# Connector.net
KiCad netlist of a schematic drawn in Altium Designer
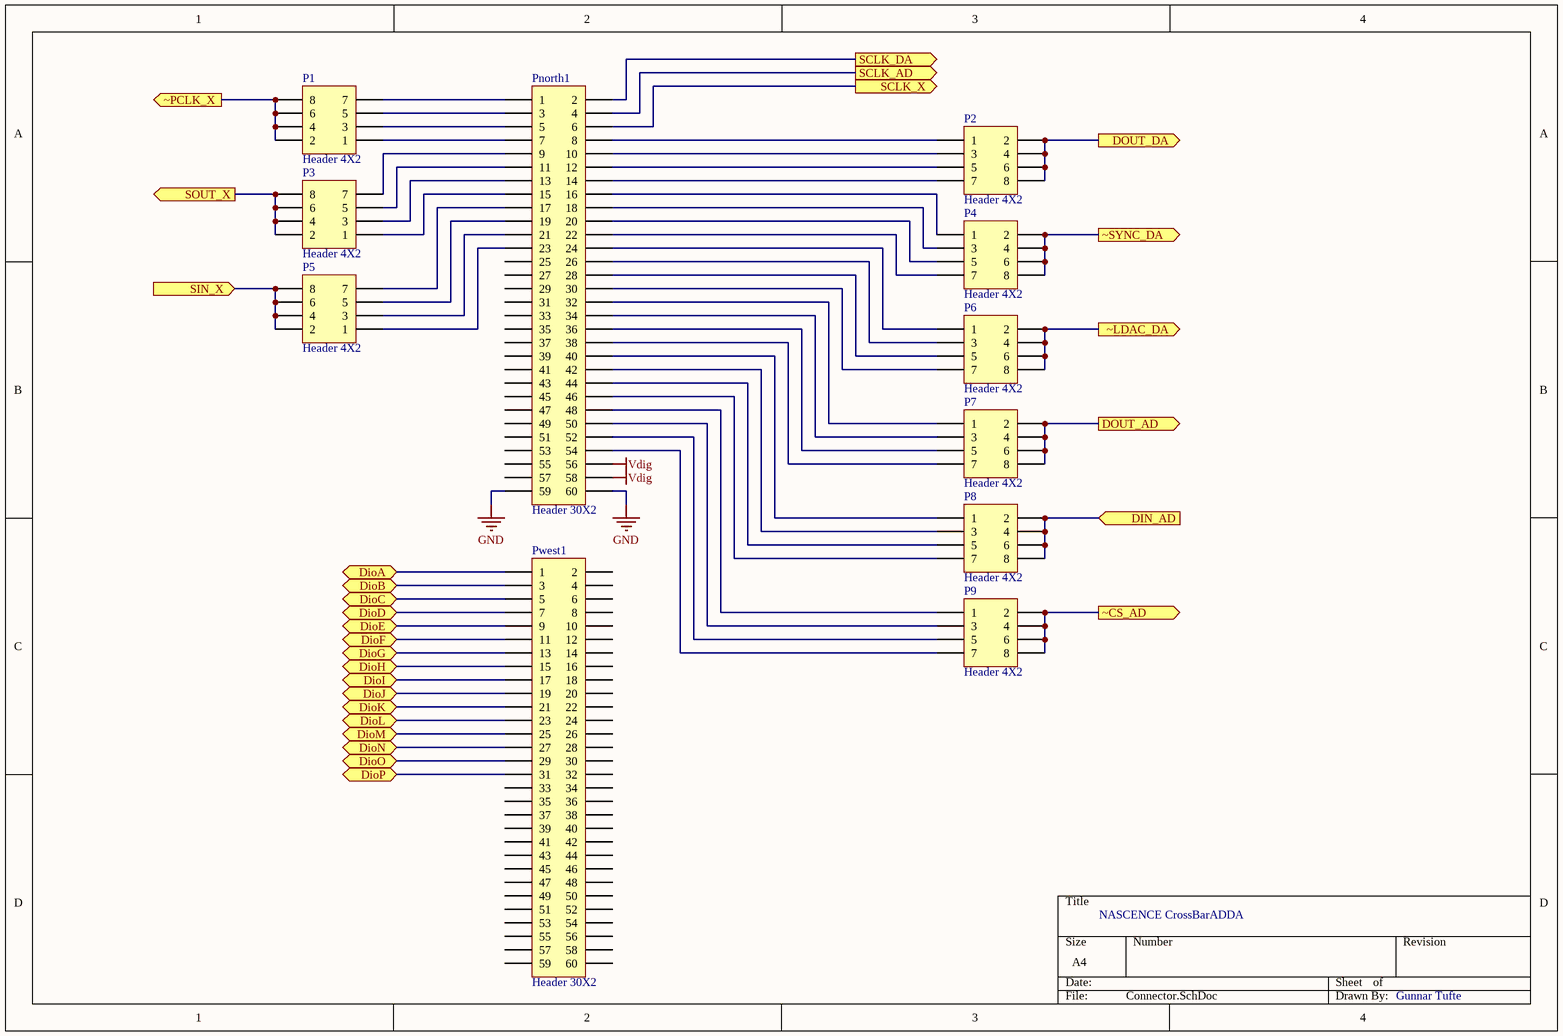
[diagram p0: Connector.SchDoc]

(export (version "E")
  (design (tool "Eeschema 10.0.6"))
  (components
    (comp (ref "P1")
      (value "Header 4X2")
      (footprint "HDR2X4")
      (description "Header, 4-Pin, Dual row")
      (fields (field (name "PUBLISHER") "Altium Limited"))
      (libsource (lib "Miscellaneous Connectors") (part "Header 4X2"))
    )
    (comp (ref "P2")
      (value "Header 4X2")
      (footprint "HDR2X4")
      (description "Header, 4-Pin, Dual row")
      (fields (field (name "PUBLISHER") "Altium Limited"))
      (libsource (lib "") (part "Header 4X2_1"))
    )
    (comp (ref "P3")
      (value "Header 4X2")
      (footprint "HDR2X4")
      (description "Header, 4-Pin, Dual row")
      (fields (field (name "PUBLISHER") "Altium Limited"))
      (libsource (lib "Miscellaneous Connectors") (part "Header 4X2"))
    )
    (comp (ref "P4")
      (value "Header 4X2")
      (footprint "HDR2X4")
      (description "Header, 4-Pin, Dual row")
      (fields (field (name "PUBLISHER") "Altium Limited"))
      (libsource (lib "") (part "Header 4X2_1"))
    )
    (comp (ref "P5")
      (value "Header 4X2")
      (footprint "HDR2X4")
      (description "Header, 4-Pin, Dual row")
      (fields (field (name "PUBLISHER") "Altium Limited"))
      (libsource (lib "Miscellaneous Connectors") (part "Header 4X2"))
    )
    (comp (ref "P6")
      (value "Header 4X2")
      (footprint "HDR2X4")
      (description "Header, 4-Pin, Dual row")
      (fields (field (name "PUBLISHER") "Altium Limited"))
      (libsource (lib "") (part "Header 4X2_1"))
    )
    (comp (ref "P7")
      (value "Header 4X2")
      (footprint "HDR2X4")
      (description "Header, 4-Pin, Dual row")
      (fields (field (name "PUBLISHER") "Altium Limited"))
      (libsource (lib "") (part "Header 4X2_1"))
    )
    (comp (ref "P8")
      (value "Header 4X2")
      (footprint "HDR2X4")
      (description "Header, 4-Pin, Dual row")
      (fields (field (name "PUBLISHER") "Altium Limited"))
      (libsource (lib "") (part "Header 4X2_1"))
    )
    (comp (ref "P9")
      (value "Header 4X2")
      (footprint "HDR2X4")
      (description "Header, 4-Pin, Dual row")
      (fields (field (name "PUBLISHER") "Altium Limited"))
      (libsource (lib "") (part "Header 4X2_1"))
    )
    (comp (ref "Pnorth1")
      (value "Header 30X2")
      (footprint "HDR2X30")
      (description "Header, 30-Pin, Dual row")
      (fields (field (name "PUBLISHER") "Altium Limited"))
      (libsource (lib "Miscellaneous Connectors") (part "Header 30X2"))
    )
    (comp (ref "Pwest1")
      (value "Header 30X2")
      (footprint "HDR2X30")
      (description "Header, 30-Pin, Dual row")
      (fields (field (name "PUBLISHER") "Altium Limited"))
      (libsource (lib "Miscellaneous Connectors") (part "Header 30X2"))
    )
  )
  (nets
    (net (code "1") (name "/DIN_AD") (class "Default")
      (node (ref "P8") (pin "2") (pinfunction "2_2") (pintype "passive"))
      (node (ref "P8") (pin "4") (pinfunction "4_4") (pintype "passive"))
      (node (ref "P8") (pin "6") (pinfunction "6_6") (pintype "passive"))
      (node (ref "P8") (pin "8") (pinfunction "8_8") (pintype "passive"))
    )
    (net (code "2") (name "/DOUT_AD") (class "Default")
      (node (ref "P7") (pin "2") (pinfunction "2_2") (pintype "passive"))
      (node (ref "P7") (pin "4") (pinfunction "4_4") (pintype "passive"))
      (node (ref "P7") (pin "6") (pinfunction "6_6") (pintype "passive"))
      (node (ref "P7") (pin "8") (pinfunction "8_8") (pintype "passive"))
    )
    (net (code "3") (name "/DOUT_DA") (class "Default")
      (node (ref "P2") (pin "2") (pinfunction "2_2") (pintype "passive"))
      (node (ref "P2") (pin "4") (pinfunction "4_4") (pintype "passive"))
      (node (ref "P2") (pin "6") (pinfunction "6_6") (pintype "passive"))
      (node (ref "P2") (pin "8") (pinfunction "8_8") (pintype "passive"))
    )
    (net (code "4") (name "/DioA") (class "Default")
      (node (ref "Pwest1") (pin "1") (pinfunction "1_1") (pintype "passive"))
    )
    (net (code "5") (name "/DioB") (class "Default")
      (node (ref "Pwest1") (pin "3") (pinfunction "3_3") (pintype "passive"))
    )
    (net (code "6") (name "/DioC") (class "Default")
      (node (ref "Pwest1") (pin "5") (pinfunction "5_5") (pintype "passive"))
    )
    (net (code "7") (name "/DioD") (class "Default")
      (node (ref "Pwest1") (pin "7") (pinfunction "7_7") (pintype "passive"))
    )
    (net (code "8") (name "/DioE") (class "Default")
      (node (ref "Pwest1") (pin "9") (pinfunction "9_9") (pintype "passive"))
    )
    (net (code "9") (name "/DioF") (class "Default")
      (node (ref "Pwest1") (pin "11") (pinfunction "11_11") (pintype "passive"))
    )
    (net (code "10") (name "/DioG") (class "Default")
      (node (ref "Pwest1") (pin "13") (pinfunction "13_13") (pintype "passive"))
    )
    (net (code "11") (name "/DioH") (class "Default")
      (node (ref "Pwest1") (pin "15") (pinfunction "15_15") (pintype "passive"))
    )
    (net (code "12") (name "/DioI") (class "Default")
      (node (ref "Pwest1") (pin "17") (pinfunction "17_17") (pintype "passive"))
    )
    (net (code "13") (name "/DioJ") (class "Default")
      (node (ref "Pwest1") (pin "19") (pinfunction "19_19") (pintype "passive"))
    )
    (net (code "14") (name "/DioK") (class "Default")
      (node (ref "Pwest1") (pin "21") (pinfunction "21_21") (pintype "passive"))
    )
    (net (code "15") (name "/DioL") (class "Default")
      (node (ref "Pwest1") (pin "23") (pinfunction "23_23") (pintype "passive"))
    )
    (net (code "16") (name "/DioM") (class "Default")
      (node (ref "Pwest1") (pin "25") (pinfunction "25_25") (pintype "passive"))
    )
    (net (code "17") (name "/DioN") (class "Default")
      (node (ref "Pwest1") (pin "27") (pinfunction "27_27") (pintype "passive"))
    )
    (net (code "18") (name "/DioO") (class "Default")
      (node (ref "Pwest1") (pin "29") (pinfunction "29_29") (pintype "passive"))
    )
    (net (code "19") (name "/DioP") (class "Default")
      (node (ref "Pwest1") (pin "31") (pinfunction "31_31") (pintype "passive"))
    )
    (net (code "20") (name "/SCLK_AD") (class "Default")
      (node (ref "Pnorth1") (pin "4") (pinfunction "4_4") (pintype "passive"))
    )
    (net (code "21") (name "/SCLK_DA") (class "Default")
      (node (ref "Pnorth1") (pin "2") (pinfunction "2_2") (pintype "passive"))
    )
    (net (code "22") (name "/SCLK_X") (class "Default")
      (node (ref "Pnorth1") (pin "6") (pinfunction "6_6") (pintype "passive"))
    )
    (net (code "23") (name "/SIN_X") (class "Default")
      (node (ref "P5") (pin "2") (pinfunction "2_2") (pintype "passive"))
      (node (ref "P5") (pin "4") (pinfunction "4_4") (pintype "passive"))
      (node (ref "P5") (pin "6") (pinfunction "6_6") (pintype "passive"))
      (node (ref "P5") (pin "8") (pinfunction "8_8") (pintype "passive"))
    )
    (net (code "24") (name "/SOUT_X") (class "Default")
      (node (ref "P3") (pin "2") (pinfunction "2_2") (pintype "passive"))
      (node (ref "P3") (pin "4") (pinfunction "4_4") (pintype "passive"))
      (node (ref "P3") (pin "6") (pinfunction "6_6") (pintype "passive"))
      (node (ref "P3") (pin "8") (pinfunction "8_8") (pintype "passive"))
    )
    (net (code "25") (name "/~CS_AD") (class "Default")
      (node (ref "P9") (pin "2") (pinfunction "2_2") (pintype "passive"))
      (node (ref "P9") (pin "4") (pinfunction "4_4") (pintype "passive"))
      (node (ref "P9") (pin "6") (pinfunction "6_6") (pintype "passive"))
      (node (ref "P9") (pin "8") (pinfunction "8_8") (pintype "passive"))
    )
    (net (code "26") (name "/~LDAC_DA") (class "Default")
      (node (ref "P6") (pin "2") (pinfunction "2_2") (pintype "passive"))
      (node (ref "P6") (pin "4") (pinfunction "4_4") (pintype "passive"))
      (node (ref "P6") (pin "6") (pinfunction "6_6") (pintype "passive"))
      (node (ref "P6") (pin "8") (pinfunction "8_8") (pintype "passive"))
    )
    (net (code "27") (name "/~PCLK_X") (class "Default")
      (node (ref "P1") (pin "2") (pinfunction "2_2") (pintype "passive"))
      (node (ref "P1") (pin "4") (pinfunction "4_4") (pintype "passive"))
      (node (ref "P1") (pin "6") (pinfunction "6_6") (pintype "passive"))
      (node (ref "P1") (pin "8") (pinfunction "8_8") (pintype "passive"))
    )
    (net (code "28") (name "/~SYNC_DA") (class "Default")
      (node (ref "P4") (pin "2") (pinfunction "2_2") (pintype "passive"))
      (node (ref "P4") (pin "4") (pinfunction "4_4") (pintype "passive"))
      (node (ref "P4") (pin "6") (pinfunction "6_6") (pintype "passive"))
      (node (ref "P4") (pin "8") (pinfunction "8_8") (pintype "passive"))
    )
    (net (code "29") (name "GND") (class "Default")
      (node (ref "Pnorth1") (pin "59") (pinfunction "59_59") (pintype "passive"))
      (node (ref "Pnorth1") (pin "60") (pinfunction "60_60") (pintype "passive"))
    )
    (net (code "30") (name "Net-(P1-Pad1)") (class "Default")
      (node (ref "P1") (pin "1") (pinfunction "1_1") (pintype "passive"))
      (node (ref "Pnorth1") (pin "7") (pinfunction "7_7") (pintype "passive"))
    )
    (net (code "31") (name "Net-(P1-Pad3)") (class "Default")
      (node (ref "P1") (pin "3") (pinfunction "3_3") (pintype "passive"))
      (node (ref "Pnorth1") (pin "5") (pinfunction "5_5") (pintype "passive"))
    )
    (net (code "32") (name "Net-(P1-Pad5)") (class "Default")
      (node (ref "P1") (pin "5") (pinfunction "5_5") (pintype "passive"))
      (node (ref "Pnorth1") (pin "3") (pinfunction "3_3") (pintype "passive"))
    )
    (net (code "33") (name "Net-(P1-Pad7)") (class "Default")
      (node (ref "P1") (pin "7") (pinfunction "7_7") (pintype "passive"))
      (node (ref "Pnorth1") (pin "1") (pinfunction "1_1") (pintype "passive"))
    )
    (net (code "34") (name "Net-(P2-Pad1)") (class "Default")
      (node (ref "P2") (pin "1") (pinfunction "1_1") (pintype "passive"))
      (node (ref "Pnorth1") (pin "8") (pinfunction "8_8") (pintype "passive"))
    )
    (net (code "35") (name "Net-(P2-Pad3)") (class "Default")
      (node (ref "P2") (pin "3") (pinfunction "3_3") (pintype "passive"))
      (node (ref "Pnorth1") (pin "10") (pinfunction "10_10") (pintype "passive"))
    )
    (net (code "36") (name "Net-(P2-Pad5)") (class "Default")
      (node (ref "P2") (pin "5") (pinfunction "5_5") (pintype "passive"))
      (node (ref "Pnorth1") (pin "12") (pinfunction "12_12") (pintype "passive"))
    )
    (net (code "37") (name "Net-(P2-Pad7)") (class "Default")
      (node (ref "P2") (pin "7") (pinfunction "7_7") (pintype "passive"))
      (node (ref "Pnorth1") (pin "14") (pinfunction "14_14") (pintype "passive"))
    )
    (net (code "38") (name "Net-(P3-Pad1)") (class "Default")
      (node (ref "P3") (pin "1") (pinfunction "1_1") (pintype "passive"))
      (node (ref "Pnorth1") (pin "15") (pinfunction "15_15") (pintype "passive"))
    )
    (net (code "39") (name "Net-(P3-Pad3)") (class "Default")
      (node (ref "P3") (pin "3") (pinfunction "3_3") (pintype "passive"))
      (node (ref "Pnorth1") (pin "13") (pinfunction "13_13") (pintype "passive"))
    )
    (net (code "40") (name "Net-(P3-Pad5)") (class "Default")
      (node (ref "P3") (pin "5") (pinfunction "5_5") (pintype "passive"))
      (node (ref "Pnorth1") (pin "11") (pinfunction "11_11") (pintype "passive"))
    )
    (net (code "41") (name "Net-(P3-Pad7)") (class "Default")
      (node (ref "P3") (pin "7") (pinfunction "7_7") (pintype "passive"))
      (node (ref "Pnorth1") (pin "9") (pinfunction "9_9") (pintype "passive"))
    )
    (net (code "42") (name "Net-(P4-Pad1)") (class "Default")
      (node (ref "P4") (pin "1") (pinfunction "1_1") (pintype "passive"))
      (node (ref "Pnorth1") (pin "16") (pinfunction "16_16") (pintype "passive"))
    )
    (net (code "43") (name "Net-(P4-Pad3)") (class "Default")
      (node (ref "P4") (pin "3") (pinfunction "3_3") (pintype "passive"))
      (node (ref "Pnorth1") (pin "18") (pinfunction "18_18") (pintype "passive"))
    )
    (net (code "44") (name "Net-(P4-Pad5)") (class "Default")
      (node (ref "P4") (pin "5") (pinfunction "5_5") (pintype "passive"))
      (node (ref "Pnorth1") (pin "20") (pinfunction "20_20") (pintype "passive"))
    )
    (net (code "45") (name "Net-(P4-Pad7)") (class "Default")
      (node (ref "P4") (pin "7") (pinfunction "7_7") (pintype "passive"))
      (node (ref "Pnorth1") (pin "22") (pinfunction "22_22") (pintype "passive"))
    )
    (net (code "46") (name "Net-(P5-Pad1)") (class "Default")
      (node (ref "P5") (pin "1") (pinfunction "1_1") (pintype "passive"))
      (node (ref "Pnorth1") (pin "23") (pinfunction "23_23") (pintype "passive"))
    )
    (net (code "47") (name "Net-(P5-Pad3)") (class "Default")
      (node (ref "P5") (pin "3") (pinfunction "3_3") (pintype "passive"))
      (node (ref "Pnorth1") (pin "21") (pinfunction "21_21") (pintype "passive"))
    )
    (net (code "48") (name "Net-(P5-Pad5)") (class "Default")
      (node (ref "P5") (pin "5") (pinfunction "5_5") (pintype "passive"))
      (node (ref "Pnorth1") (pin "19") (pinfunction "19_19") (pintype "passive"))
    )
    (net (code "49") (name "Net-(P5-Pad7)") (class "Default")
      (node (ref "P5") (pin "7") (pinfunction "7_7") (pintype "passive"))
      (node (ref "Pnorth1") (pin "17") (pinfunction "17_17") (pintype "passive"))
    )
    (net (code "50") (name "Net-(P6-Pad1)") (class "Default")
      (node (ref "P6") (pin "1") (pinfunction "1_1") (pintype "passive"))
      (node (ref "Pnorth1") (pin "24") (pinfunction "24_24") (pintype "passive"))
    )
    (net (code "51") (name "Net-(P6-Pad3)") (class "Default")
      (node (ref "P6") (pin "3") (pinfunction "3_3") (pintype "passive"))
      (node (ref "Pnorth1") (pin "26") (pinfunction "26_26") (pintype "passive"))
    )
    (net (code "52") (name "Net-(P6-Pad5)") (class "Default")
      (node (ref "P6") (pin "5") (pinfunction "5_5") (pintype "passive"))
      (node (ref "Pnorth1") (pin "28") (pinfunction "28_28") (pintype "passive"))
    )
    (net (code "53") (name "Net-(P6-Pad7)") (class "Default")
      (node (ref "P6") (pin "7") (pinfunction "7_7") (pintype "passive"))
      (node (ref "Pnorth1") (pin "30") (pinfunction "30_30") (pintype "passive"))
    )
    (net (code "54") (name "Net-(P7-Pad1)") (class "Default")
      (node (ref "P7") (pin "1") (pinfunction "1_1") (pintype "passive"))
      (node (ref "Pnorth1") (pin "32") (pinfunction "32_32") (pintype "passive"))
    )
    (net (code "55") (name "Net-(P7-Pad3)") (class "Default")
      (node (ref "P7") (pin "3") (pinfunction "3_3") (pintype "passive"))
      (node (ref "Pnorth1") (pin "34") (pinfunction "34_34") (pintype "passive"))
    )
    (net (code "56") (name "Net-(P7-Pad5)") (class "Default")
      (node (ref "P7") (pin "5") (pinfunction "5_5") (pintype "passive"))
      (node (ref "Pnorth1") (pin "36") (pinfunction "36_36") (pintype "passive"))
    )
    (net (code "57") (name "Net-(P7-Pad7)") (class "Default")
      (node (ref "P7") (pin "7") (pinfunction "7_7") (pintype "passive"))
      (node (ref "Pnorth1") (pin "38") (pinfunction "38_38") (pintype "passive"))
    )
    (net (code "58") (name "Net-(P8-Pad1)") (class "Default")
      (node (ref "P8") (pin "1") (pinfunction "1_1") (pintype "passive"))
      (node (ref "Pnorth1") (pin "40") (pinfunction "40_40") (pintype "passive"))
    )
    (net (code "59") (name "Net-(P8-Pad3)") (class "Default")
      (node (ref "P8") (pin "3") (pinfunction "3_3") (pintype "passive"))
      (node (ref "Pnorth1") (pin "42") (pinfunction "42_42") (pintype "passive"))
    )
    (net (code "60") (name "Net-(P8-Pad5)") (class "Default")
      (node (ref "P8") (pin "5") (pinfunction "5_5") (pintype "passive"))
      (node (ref "Pnorth1") (pin "44") (pinfunction "44_44") (pintype "passive"))
    )
    (net (code "61") (name "Net-(P8-Pad7)") (class "Default")
      (node (ref "P8") (pin "7") (pinfunction "7_7") (pintype "passive"))
      (node (ref "Pnorth1") (pin "46") (pinfunction "46_46") (pintype "passive"))
    )
    (net (code "62") (name "Net-(P9-Pad1)") (class "Default")
      (node (ref "P9") (pin "1") (pinfunction "1_1") (pintype "passive"))
      (node (ref "Pnorth1") (pin "48") (pinfunction "48_48") (pintype "passive"))
    )
    (net (code "63") (name "Net-(P9-Pad3)") (class "Default")
      (node (ref "P9") (pin "3") (pinfunction "3_3") (pintype "passive"))
      (node (ref "Pnorth1") (pin "50") (pinfunction "50_50") (pintype "passive"))
    )
    (net (code "64") (name "Net-(P9-Pad5)") (class "Default")
      (node (ref "P9") (pin "5") (pinfunction "5_5") (pintype "passive"))
      (node (ref "Pnorth1") (pin "52") (pinfunction "52_52") (pintype "passive"))
    )
    (net (code "65") (name "Net-(P9-Pad7)") (class "Default")
      (node (ref "P9") (pin "7") (pinfunction "7_7") (pintype "passive"))
      (node (ref "Pnorth1") (pin "54") (pinfunction "54_54") (pintype "passive"))
    )
    (net (code "66") (name "Vdig") (class "Default")
      (node (ref "Pnorth1") (pin "56") (pinfunction "56_56") (pintype "passive"))
      (node (ref "Pnorth1") (pin "58") (pinfunction "58_58") (pintype "passive"))
    )
    (net (code "67") (name "unconnected-(Pnorth1-Pad25)") (class "Default")
      (node (ref "Pnorth1") (pin "25") (pinfunction "25_25") (pintype "passive"))
    )
    (net (code "68") (name "unconnected-(Pnorth1-Pad27)") (class "Default")
      (node (ref "Pnorth1") (pin "27") (pinfunction "27_27") (pintype "passive"))
    )
    (net (code "69") (name "unconnected-(Pnorth1-Pad29)") (class "Default")
      (node (ref "Pnorth1") (pin "29") (pinfunction "29_29") (pintype "passive"))
    )
    (net (code "70") (name "unconnected-(Pnorth1-Pad31)") (class "Default")
      (node (ref "Pnorth1") (pin "31") (pinfunction "31_31") (pintype "passive"))
    )
    (net (code "71") (name "unconnected-(Pnorth1-Pad33)") (class "Default")
      (node (ref "Pnorth1") (pin "33") (pinfunction "33_33") (pintype "passive"))
    )
    (net (code "72") (name "unconnected-(Pnorth1-Pad35)") (class "Default")
      (node (ref "Pnorth1") (pin "35") (pinfunction "35_35") (pintype "passive"))
    )
    (net (code "73") (name "unconnected-(Pnorth1-Pad37)") (class "Default")
      (node (ref "Pnorth1") (pin "37") (pinfunction "37_37") (pintype "passive"))
    )
    (net (code "74") (name "unconnected-(Pnorth1-Pad39)") (class "Default")
      (node (ref "Pnorth1") (pin "39") (pinfunction "39_39") (pintype "passive"))
    )
    (net (code "75") (name "unconnected-(Pnorth1-Pad41)") (class "Default")
      (node (ref "Pnorth1") (pin "41") (pinfunction "41_41") (pintype "passive"))
    )
    (net (code "76") (name "unconnected-(Pnorth1-Pad43)") (class "Default")
      (node (ref "Pnorth1") (pin "43") (pinfunction "43_43") (pintype "passive"))
    )
    (net (code "77") (name "unconnected-(Pnorth1-Pad45)") (class "Default")
      (node (ref "Pnorth1") (pin "45") (pinfunction "45_45") (pintype "passive"))
    )
    (net (code "78") (name "unconnected-(Pnorth1-Pad47)") (class "Default")
      (node (ref "Pnorth1") (pin "47") (pinfunction "47_47") (pintype "passive"))
    )
    (net (code "79") (name "unconnected-(Pnorth1-Pad49)") (class "Default")
      (node (ref "Pnorth1") (pin "49") (pinfunction "49_49") (pintype "passive"))
    )
    (net (code "80") (name "unconnected-(Pnorth1-Pad51)") (class "Default")
      (node (ref "Pnorth1") (pin "51") (pinfunction "51_51") (pintype "passive"))
    )
    (net (code "81") (name "unconnected-(Pnorth1-Pad53)") (class "Default")
      (node (ref "Pnorth1") (pin "53") (pinfunction "53_53") (pintype "passive"))
    )
    (net (code "82") (name "unconnected-(Pnorth1-Pad55)") (class "Default")
      (node (ref "Pnorth1") (pin "55") (pinfunction "55_55") (pintype "passive"))
    )
    (net (code "83") (name "unconnected-(Pnorth1-Pad57)") (class "Default")
      (node (ref "Pnorth1") (pin "57") (pinfunction "57_57") (pintype "passive"))
    )
    (net (code "84") (name "unconnected-(Pwest1-Pad2)") (class "Default")
      (node (ref "Pwest1") (pin "2") (pinfunction "2_2") (pintype "passive"))
    )
    (net (code "85") (name "unconnected-(Pwest1-Pad4)") (class "Default")
      (node (ref "Pwest1") (pin "4") (pinfunction "4_4") (pintype "passive"))
    )
    (net (code "86") (name "unconnected-(Pwest1-Pad6)") (class "Default")
      (node (ref "Pwest1") (pin "6") (pinfunction "6_6") (pintype "passive"))
    )
    (net (code "87") (name "unconnected-(Pwest1-Pad8)") (class "Default")
      (node (ref "Pwest1") (pin "8") (pinfunction "8_8") (pintype "passive"))
    )
    (net (code "88") (name "unconnected-(Pwest1-Pad10)") (class "Default")
      (node (ref "Pwest1") (pin "10") (pinfunction "10_10") (pintype "passive"))
    )
    (net (code "89") (name "unconnected-(Pwest1-Pad12)") (class "Default")
      (node (ref "Pwest1") (pin "12") (pinfunction "12_12") (pintype "passive"))
    )
    (net (code "90") (name "unconnected-(Pwest1-Pad14)") (class "Default")
      (node (ref "Pwest1") (pin "14") (pinfunction "14_14") (pintype "passive"))
    )
    (net (code "91") (name "unconnected-(Pwest1-Pad16)") (class "Default")
      (node (ref "Pwest1") (pin "16") (pinfunction "16_16") (pintype "passive"))
    )
    (net (code "92") (name "unconnected-(Pwest1-Pad18)") (class "Default")
      (node (ref "Pwest1") (pin "18") (pinfunction "18_18") (pintype "passive"))
    )
    (net (code "93") (name "unconnected-(Pwest1-Pad20)") (class "Default")
      (node (ref "Pwest1") (pin "20") (pinfunction "20_20") (pintype "passive"))
    )
    (net (code "94") (name "unconnected-(Pwest1-Pad22)") (class "Default")
      (node (ref "Pwest1") (pin "22") (pinfunction "22_22") (pintype "passive"))
    )
    (net (code "95") (name "unconnected-(Pwest1-Pad24)") (class "Default")
      (node (ref "Pwest1") (pin "24") (pinfunction "24_24") (pintype "passive"))
    )
    (net (code "96") (name "unconnected-(Pwest1-Pad26)") (class "Default")
      (node (ref "Pwest1") (pin "26") (pinfunction "26_26") (pintype "passive"))
    )
    (net (code "97") (name "unconnected-(Pwest1-Pad28)") (class "Default")
      (node (ref "Pwest1") (pin "28") (pinfunction "28_28") (pintype "passive"))
    )
    (net (code "98") (name "unconnected-(Pwest1-Pad30)") (class "Default")
      (node (ref "Pwest1") (pin "30") (pinfunction "30_30") (pintype "passive"))
    )
    (net (code "99") (name "unconnected-(Pwest1-Pad32)") (class "Default")
      (node (ref "Pwest1") (pin "32") (pinfunction "32_32") (pintype "passive"))
    )
    (net (code "100") (name "unconnected-(Pwest1-Pad33)") (class "Default")
      (node (ref "Pwest1") (pin "33") (pinfunction "33_33") (pintype "passive"))
    )
    (net (code "101") (name "unconnected-(Pwest1-Pad34)") (class "Default")
      (node (ref "Pwest1") (pin "34") (pinfunction "34_34") (pintype "passive"))
    )
    (net (code "102") (name "unconnected-(Pwest1-Pad35)") (class "Default")
      (node (ref "Pwest1") (pin "35") (pinfunction "35_35") (pintype "passive"))
    )
    (net (code "103") (name "unconnected-(Pwest1-Pad36)") (class "Default")
      (node (ref "Pwest1") (pin "36") (pinfunction "36_36") (pintype "passive"))
    )
    (net (code "104") (name "unconnected-(Pwest1-Pad37)") (class "Default")
      (node (ref "Pwest1") (pin "37") (pinfunction "37_37") (pintype "passive"))
    )
    (net (code "105") (name "unconnected-(Pwest1-Pad38)") (class "Default")
      (node (ref "Pwest1") (pin "38") (pinfunction "38_38") (pintype "passive"))
    )
    (net (code "106") (name "unconnected-(Pwest1-Pad39)") (class "Default")
      (node (ref "Pwest1") (pin "39") (pinfunction "39_39") (pintype "passive"))
    )
    (net (code "107") (name "unconnected-(Pwest1-Pad40)") (class "Default")
      (node (ref "Pwest1") (pin "40") (pinfunction "40_40") (pintype "passive"))
    )
    (net (code "108") (name "unconnected-(Pwest1-Pad41)") (class "Default")
      (node (ref "Pwest1") (pin "41") (pinfunction "41_41") (pintype "passive"))
    )
    (net (code "109") (name "unconnected-(Pwest1-Pad42)") (class "Default")
      (node (ref "Pwest1") (pin "42") (pinfunction "42_42") (pintype "passive"))
    )
    (net (code "110") (name "unconnected-(Pwest1-Pad43)") (class "Default")
      (node (ref "Pwest1") (pin "43") (pinfunction "43_43") (pintype "passive"))
    )
    (net (code "111") (name "unconnected-(Pwest1-Pad44)") (class "Default")
      (node (ref "Pwest1") (pin "44") (pinfunction "44_44") (pintype "passive"))
    )
    (net (code "112") (name "unconnected-(Pwest1-Pad45)") (class "Default")
      (node (ref "Pwest1") (pin "45") (pinfunction "45_45") (pintype "passive"))
    )
    (net (code "113") (name "unconnected-(Pwest1-Pad46)") (class "Default")
      (node (ref "Pwest1") (pin "46") (pinfunction "46_46") (pintype "passive"))
    )
    (net (code "114") (name "unconnected-(Pwest1-Pad47)") (class "Default")
      (node (ref "Pwest1") (pin "47") (pinfunction "47_47") (pintype "passive"))
    )
    (net (code "115") (name "unconnected-(Pwest1-Pad48)") (class "Default")
      (node (ref "Pwest1") (pin "48") (pinfunction "48_48") (pintype "passive"))
    )
    (net (code "116") (name "unconnected-(Pwest1-Pad49)") (class "Default")
      (node (ref "Pwest1") (pin "49") (pinfunction "49_49") (pintype "passive"))
    )
    (net (code "117") (name "unconnected-(Pwest1-Pad50)") (class "Default")
      (node (ref "Pwest1") (pin "50") (pinfunction "50_50") (pintype "passive"))
    )
    (net (code "118") (name "unconnected-(Pwest1-Pad51)") (class "Default")
      (node (ref "Pwest1") (pin "51") (pinfunction "51_51") (pintype "passive"))
    )
    (net (code "119") (name "unconnected-(Pwest1-Pad52)") (class "Default")
      (node (ref "Pwest1") (pin "52") (pinfunction "52_52") (pintype "passive"))
    )
    (net (code "120") (name "unconnected-(Pwest1-Pad53)") (class "Default")
      (node (ref "Pwest1") (pin "53") (pinfunction "53_53") (pintype "passive"))
    )
    (net (code "121") (name "unconnected-(Pwest1-Pad54)") (class "Default")
      (node (ref "Pwest1") (pin "54") (pinfunction "54_54") (pintype "passive"))
    )
    (net (code "122") (name "unconnected-(Pwest1-Pad55)") (class "Default")
      (node (ref "Pwest1") (pin "55") (pinfunction "55_55") (pintype "passive"))
    )
    (net (code "123") (name "unconnected-(Pwest1-Pad56)") (class "Default")
      (node (ref "Pwest1") (pin "56") (pinfunction "56_56") (pintype "passive"))
    )
    (net (code "124") (name "unconnected-(Pwest1-Pad57)") (class "Default")
      (node (ref "Pwest1") (pin "57") (pinfunction "57_57") (pintype "passive"))
    )
    (net (code "125") (name "unconnected-(Pwest1-Pad58)") (class "Default")
      (node (ref "Pwest1") (pin "58") (pinfunction "58_58") (pintype "passive"))
    )
    (net (code "126") (name "unconnected-(Pwest1-Pad59)") (class "Default")
      (node (ref "Pwest1") (pin "59") (pinfunction "59_59") (pintype "passive"))
    )
    (net (code "127") (name "unconnected-(Pwest1-Pad60)") (class "Default")
      (node (ref "Pwest1") (pin "60") (pinfunction "60_60") (pintype "passive"))
    )
  )
)
